# GSM_Unit.net
KiCad netlist of a schematic drawn in Altium Designer
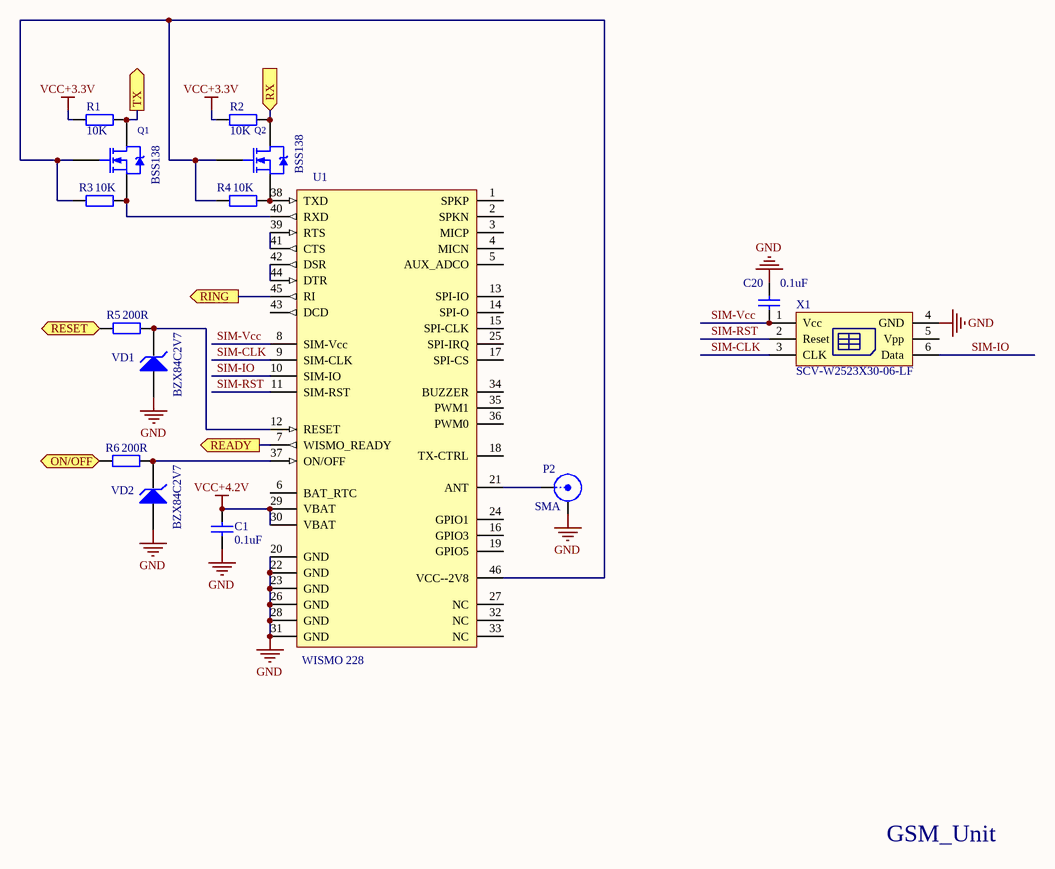
[diagram p0: GSM_Unit.SchDoc]

(export (version "E")
  (design (tool "Eeschema 10.0.6"))
  (components
    (comp (ref "C1")
      (value "0.1uF")
      (footprint "C0603")
      (description "Capasitor_SMD_0808/")
      (fields (field (name "Comment") "CAP_SMD"))
      (libsource (lib "NEW") (part "Capasitor_SMD_0805"))
    )
    (comp (ref "C20")
      (value "0.1uF")
      (footprint "C0603")
      (description "Capasitor_SMD_0808/")
      (fields (field (name "Comment") "CAP_SMD"))
      (libsource (lib "NEW") (part "Capasitor_SMD_0805"))
    )
    (comp (ref "P2")
      (value "SMA")
      (footprint "SMA")
      (fields (field (name "PUBLISHER") "Altium Limited"))
      (libsource (lib "NEW") (part "SMA"))
    )
    (comp (ref "Q1")
      (value "BSS138")
      (footprint "SOT23")
      (description "BSS138-SOT23")
      (libsource (lib "NEW") (part "BSS138-SOT23"))
    )
    (comp (ref "Q2")
      (value "BSS138")
      (footprint "SOT23")
      (description "BSS138-SOT23")
      (libsource (lib "NEW") (part "BSS138-SOT23"))
    )
    (comp (ref "R1")
      (value "10K")
      (footprint "C0603")
      (description "Resistor")
      (fields (field (name "Comment") "RES_SMD"))
      (libsource (lib "NEW") (part "RES"))
    )
    (comp (ref "R2")
      (value "10K")
      (footprint "C0603")
      (description "Resistor")
      (fields (field (name "Comment") "RES_SMD"))
      (libsource (lib "NEW") (part "RES"))
    )
    (comp (ref "R3")
      (value "10K")
      (footprint "C0603")
      (description "Resistor")
      (fields (field (name "Comment") "RES_SMD"))
      (libsource (lib "NEW") (part "RES"))
    )
    (comp (ref "R4")
      (value "10K")
      (footprint "C0603")
      (description "Resistor")
      (fields (field (name "Comment") "RES_SMD"))
      (libsource (lib "NEW") (part "RES"))
    )
    (comp (ref "R5")
      (value "200R")
      (footprint "C0603")
      (description "Resistor")
      (fields (field (name "Comment") "RES_SMD"))
      (libsource (lib "NEW") (part "RES"))
    )
    (comp (ref "R6")
      (value "200R")
      (footprint "C0603")
      (description "Resistor")
      (fields (field (name "Comment") "RES_SMD"))
      (libsource (lib "NEW") (part "RES"))
    )
    (comp (ref "U1") (value "WISMO 228") (footprint "WISMO") (libsource (lib "NEW") (part "WISMO 228")))
    (comp (ref "VD1")
      (value "BZX84C2V7")
      (footprint "SOT23")
      (description "BZX84C")
      (libsource (lib "NEW") (part "BZX84C"))
    )
    (comp (ref "VD2")
      (value "BZX84C2V7")
      (footprint "SOT23")
      (description "BZX84C")
      (libsource (lib "NEW") (part "BZX84C"))
    )
    (comp (ref "X1")
      (value "SCV-W2523X30-06-LF")
      (footprint "SCV-W2523X30-06-LF")
      (description "SIM Cartreader")
      (libsource (lib "NEW") (part "SCV-W2523X30-06-LF"))
    )
  )
  (nets
    (net (code "1") (name "/ON{slash}OFF") (class "Default")
      (node (ref "R6") (pin "1") (pinfunction "1_1") (pintype "passive"))
    )
    (net (code "2") (name "/READY") (class "Default")
      (node (ref "U1") (pin "7") (pinfunction "WISMO_READY_7") (pintype "output"))
    )
    (net (code "3") (name "/RESET") (class "Default")
      (node (ref "R5") (pin "1") (pinfunction "1_1") (pintype "passive"))
    )
    (net (code "4") (name "/RING") (class "Default")
      (node (ref "U1") (pin "45") (pinfunction "RI_45") (pintype "output"))
    )
    (net (code "5") (name "/RX") (class "Default")
      (node (ref "Q2") (pin "3") (pinfunction "D_3") (pintype "passive"))
      (node (ref "R2") (pin "2") (pinfunction "2_2") (pintype "passive"))
    )
    (net (code "6") (name "/SIM-CLK") (class "Default")
      (node (ref "U1") (pin "9") (pinfunction "SIM-CLK_9") (pintype "passive"))
      (node (ref "X1") (pin "3") (pinfunction "CLK_3") (pintype "passive"))
    )
    (net (code "7") (name "/SIM-IO") (class "Default")
      (node (ref "U1") (pin "10") (pinfunction "SIM-IO_10") (pintype "passive"))
      (node (ref "X1") (pin "6") (pinfunction "Data_6") (pintype "passive"))
    )
    (net (code "8") (name "/SIM-RST") (class "Default")
      (node (ref "U1") (pin "11") (pinfunction "SIM-RST_11") (pintype "passive"))
      (node (ref "X1") (pin "2") (pinfunction "Reset_2") (pintype "passive"))
    )
    (net (code "9") (name "/SIM-Vcc") (class "Default")
      (node (ref "C20") (pin "2") (pinfunction "2_2") (pintype "passive"))
      (node (ref "U1") (pin "8") (pinfunction "SIM-Vcc_8") (pintype "passive"))
      (node (ref "X1") (pin "1") (pinfunction "Vcc_1") (pintype "passive"))
    )
    (net (code "10") (name "/TX") (class "Default")
      (node (ref "Q1") (pin "3") (pinfunction "D_3") (pintype "passive"))
      (node (ref "R1") (pin "2") (pinfunction "2_2") (pintype "passive"))
    )
    (net (code "11") (name "GND") (class "Default")
      (node (ref "C1") (pin "2") (pinfunction "2_2") (pintype "passive"))
      (node (ref "C20") (pin "1") (pinfunction "1_1") (pintype "passive"))
      (node (ref "P2") (pin "2") (pinfunction "Y_2") (pintype "passive"))
      (node (ref "U1") (pin "20") (pinfunction "GND_20") (pintype "passive"))
      (node (ref "U1") (pin "22") (pinfunction "GND_22") (pintype "passive"))
      (node (ref "U1") (pin "23") (pinfunction "GND_23") (pintype "passive"))
      (node (ref "U1") (pin "26") (pinfunction "GND_26") (pintype "passive"))
      (node (ref "U1") (pin "28") (pinfunction "GND_28") (pintype "passive"))
      (node (ref "U1") (pin "31") (pinfunction "GND_31") (pintype "passive"))
      (node (ref "VD1") (pin "1") (pinfunction "A_1") (pintype "passive"))
      (node (ref "VD2") (pin "1") (pinfunction "A_1") (pintype "passive"))
      (node (ref "X1") (pin "4") (pinfunction "GND_4") (pintype "passive"))
    )
    (net (code "12") (name "Net-(P2-X)") (class "Default")
      (node (ref "P2") (pin "1") (pinfunction "X_1") (pintype "passive"))
      (node (ref "U1") (pin "21") (pinfunction "ANT_21") (pintype "passive"))
    )
    (net (code "13") (name "Net-(Q1-G)") (class "Default")
      (node (ref "Q1") (pin "1") (pinfunction "G_1") (pintype "passive"))
      (node (ref "Q2") (pin "1") (pinfunction "G_1") (pintype "passive"))
      (node (ref "R3") (pin "1") (pinfunction "1_1") (pintype "passive"))
      (node (ref "R4") (pin "1") (pinfunction "1_1") (pintype "passive"))
      (node (ref "U1") (pin "46") (pinfunction "VCC--2V8_46") (pintype "passive"))
    )
    (net (code "14") (name "Net-(Q1-S)") (class "Default")
      (node (ref "Q1") (pin "2") (pinfunction "S_2") (pintype "passive"))
      (node (ref "R3") (pin "2") (pinfunction "2_2") (pintype "passive"))
      (node (ref "U1") (pin "40") (pinfunction "RXD_40") (pintype "output"))
    )
    (net (code "15") (name "Net-(Q2-S)") (class "Default")
      (node (ref "Q2") (pin "2") (pinfunction "S_2") (pintype "passive"))
      (node (ref "R4") (pin "2") (pinfunction "2_2") (pintype "passive"))
      (node (ref "U1") (pin "38") (pinfunction "TXD_38") (pintype "input"))
    )
    (net (code "16") (name "Net-(U1-CTS)") (class "Default")
      (node (ref "U1") (pin "39") (pinfunction "RTS_39") (pintype "input"))
      (node (ref "U1") (pin "41") (pinfunction "CTS_41") (pintype "output"))
    )
    (net (code "17") (name "Net-(U1-DSR)") (class "Default")
      (node (ref "U1") (pin "42") (pinfunction "DSR_42") (pintype "output"))
      (node (ref "U1") (pin "44") (pinfunction "DTR_44") (pintype "input"))
    )
    (net (code "18") (name "Net-(U1-ON{slash}OFF)") (class "Default")
      (node (ref "R6") (pin "2") (pinfunction "2_2") (pintype "passive"))
      (node (ref "U1") (pin "37") (pinfunction "ON/OFF_37") (pintype "input"))
      (node (ref "VD2") (pin "3") (pinfunction "K_3") (pintype "passive"))
    )
    (net (code "19") (name "Net-(U1-RESET)") (class "Default")
      (node (ref "R5") (pin "2") (pinfunction "2_2") (pintype "passive"))
      (node (ref "U1") (pin "12") (pinfunction "RESET_12") (pintype "input"))
      (node (ref "VD1") (pin "3") (pinfunction "K_3") (pintype "passive"))
    )
    (net (code "20") (name "VCC+3.3V") (class "Default")
      (node (ref "R1") (pin "1") (pinfunction "1_1") (pintype "passive"))
      (node (ref "R2") (pin "1") (pinfunction "1_1") (pintype "passive"))
    )
    (net (code "21") (name "VCC+4.2V") (class "Default")
      (node (ref "C1") (pin "1") (pinfunction "1_1") (pintype "passive"))
      (node (ref "U1") (pin "29") (pinfunction "VBAT_29") (pintype "passive"))
      (node (ref "U1") (pin "30") (pinfunction "VBAT_30") (pintype "passive"))
    )
    (net (code "22") (name "unconnected-(U1-AUX_ADCO-Pad5)") (class "Default")
      (node (ref "U1") (pin "5") (pinfunction "AUX_ADCO_5") (pintype "passive"))
    )
    (net (code "23") (name "unconnected-(U1-BAT_RTC-Pad6)") (class "Default")
      (node (ref "U1") (pin "6") (pinfunction "BAT_RTC_6") (pintype "passive"))
    )
    (net (code "24") (name "unconnected-(U1-BUZZER-Pad34)") (class "Default")
      (node (ref "U1") (pin "34") (pinfunction "BUZZER_34") (pintype "passive"))
    )
    (net (code "25") (name "unconnected-(U1-DCD-Pad43)") (class "Default")
      (node (ref "U1") (pin "43") (pinfunction "DCD_43") (pintype "output"))
    )
    (net (code "26") (name "unconnected-(U1-GPIO1-Pad24)") (class "Default")
      (node (ref "U1") (pin "24") (pinfunction "GPIO1_24") (pintype "passive"))
    )
    (net (code "27") (name "unconnected-(U1-GPIO3-Pad16)") (class "Default")
      (node (ref "U1") (pin "16") (pinfunction "GPIO3_16") (pintype "passive"))
    )
    (net (code "28") (name "unconnected-(U1-GPIO5-Pad19)") (class "Default")
      (node (ref "U1") (pin "19") (pinfunction "GPIO5_19") (pintype "passive"))
    )
    (net (code "29") (name "unconnected-(U1-MICN-Pad4)") (class "Default")
      (node (ref "U1") (pin "4") (pinfunction "MICN_4") (pintype "passive"))
    )
    (net (code "30") (name "unconnected-(U1-MICP-Pad3)") (class "Default")
      (node (ref "U1") (pin "3") (pinfunction "MICP_3") (pintype "passive"))
    )
    (net (code "31") (name "unconnected-(U1-NC-Pad27)") (class "Default")
      (node (ref "U1") (pin "27") (pinfunction "NC_27") (pintype "passive"))
    )
    (net (code "32") (name "unconnected-(U1-NC-Pad32)") (class "Default")
      (node (ref "U1") (pin "32") (pinfunction "NC_32") (pintype "passive"))
    )
    (net (code "33") (name "unconnected-(U1-NC-Pad33)") (class "Default")
      (node (ref "U1") (pin "33") (pinfunction "NC_33") (pintype "passive"))
    )
    (net (code "34") (name "unconnected-(U1-PWM0-Pad36)") (class "Default")
      (node (ref "U1") (pin "36") (pinfunction "PWM0_36") (pintype "passive"))
    )
    (net (code "35") (name "unconnected-(U1-PWM1-Pad35)") (class "Default")
      (node (ref "U1") (pin "35") (pinfunction "PWM1_35") (pintype "passive"))
    )
    (net (code "36") (name "unconnected-(U1-SPI-CLK-Pad15)") (class "Default")
      (node (ref "U1") (pin "15") (pinfunction "SPI-CLK_15") (pintype "passive"))
    )
    (net (code "37") (name "unconnected-(U1-SPI-CS-Pad17)") (class "Default")
      (node (ref "U1") (pin "17") (pinfunction "SPI-CS_17") (pintype "passive"))
    )
    (net (code "38") (name "unconnected-(U1-SPI-IO-Pad13)") (class "Default")
      (node (ref "U1") (pin "13") (pinfunction "SPI-IO_13") (pintype "passive"))
    )
    (net (code "39") (name "unconnected-(U1-SPI-IRQ-Pad25)") (class "Default")
      (node (ref "U1") (pin "25") (pinfunction "SPI-IRQ_25") (pintype "passive"))
    )
    (net (code "40") (name "unconnected-(U1-SPI-O-Pad14)") (class "Default")
      (node (ref "U1") (pin "14") (pinfunction "SPI-O_14") (pintype "passive"))
    )
    (net (code "41") (name "unconnected-(U1-SPKN-Pad2)") (class "Default")
      (node (ref "U1") (pin "2") (pinfunction "SPKN_2") (pintype "passive"))
    )
    (net (code "42") (name "unconnected-(U1-SPKP-Pad1)") (class "Default")
      (node (ref "U1") (pin "1") (pinfunction "SPKP_1") (pintype "passive"))
    )
    (net (code "43") (name "unconnected-(U1-TX-CTRL-Pad18)") (class "Default")
      (node (ref "U1") (pin "18") (pinfunction "TX-CTRL_18") (pintype "passive"))
    )
    (net (code "44") (name "unconnected-(VD1-Pad2)") (class "Default")
      (node (ref "VD1") (pin "2") (pintype "passive"))
    )
    (net (code "45") (name "unconnected-(VD2-Pad2)") (class "Default")
      (node (ref "VD2") (pin "2") (pintype "passive"))
    )
    (net (code "46") (name "unconnected-(X1-Vpp-Pad5)") (class "Default")
      (node (ref "X1") (pin "5") (pinfunction "Vpp_5") (pintype "passive"))
    )
  )
)
